# Central_Hub.net
KiCad netlist of a schematic drawn in EAGLE
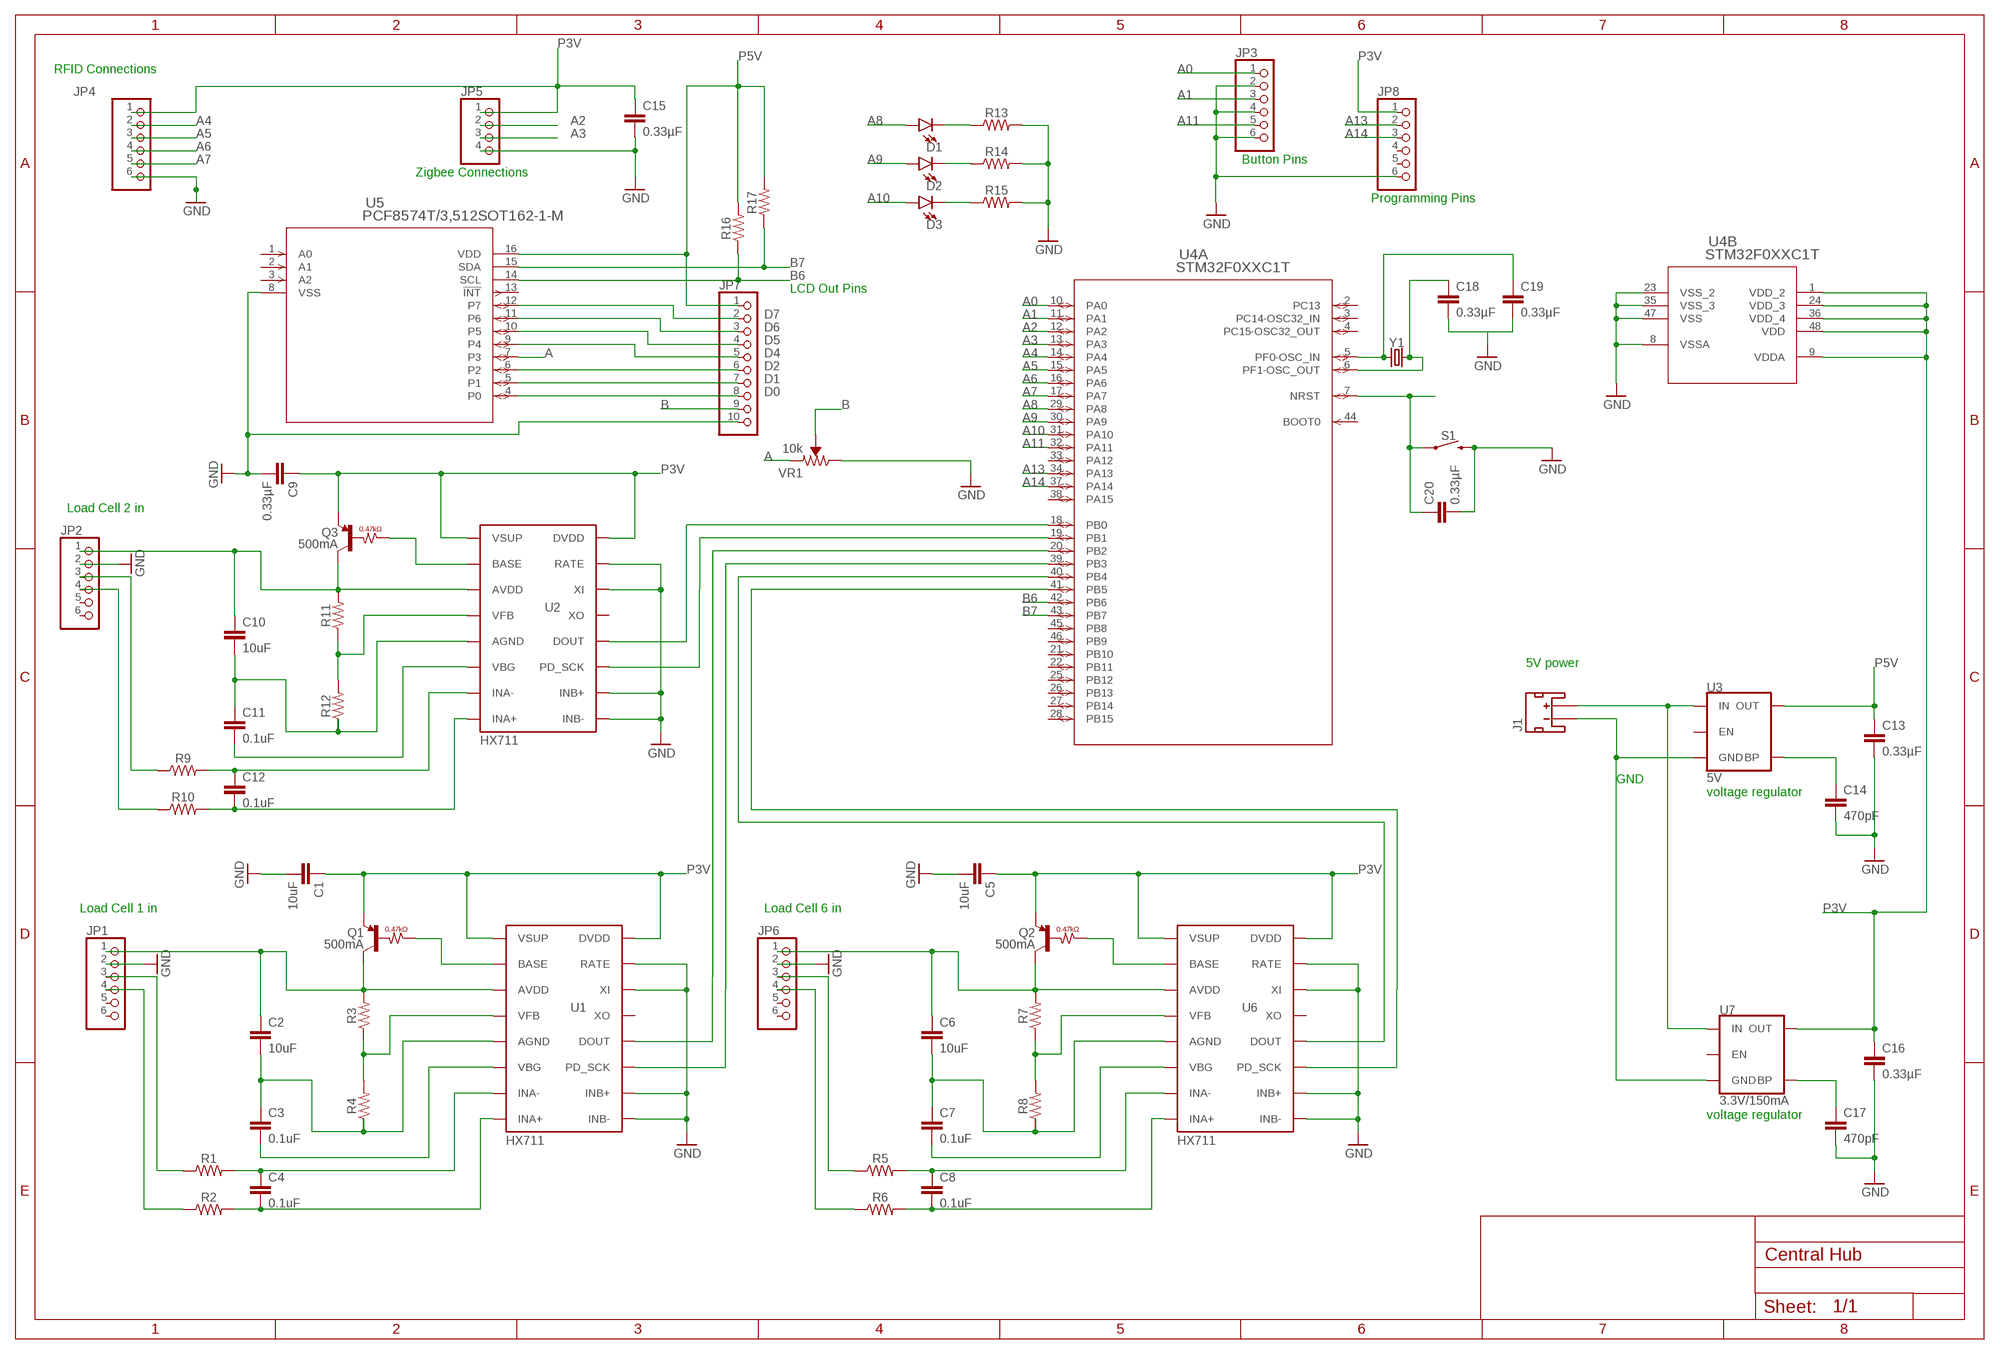
[diagram p0: schematic, sheet 1]

(export (version "E")
  (design (tool "Eeschema 10.0.6"))
  (components
    (comp (ref "C1")
      (value "10uF")
      (footprint "eagle-import:0603")
      (libsource (lib "eagle-import") (part "10UF-0603-6.3V-20%"))
    )
    (comp (ref "C2")
      (value "10uF")
      (footprint "eagle-import:0603")
      (libsource (lib "eagle-import") (part "10UF-0603-6.3V-20%"))
    )
    (comp (ref "C3")
      (value "0.1uF")
      (footprint "eagle-import:0603")
      (libsource (lib "eagle-import") (part "0.1UF-0603-25V-(+80/-20%)"))
    )
    (comp (ref "C4")
      (value "0.1uF")
      (footprint "eagle-import:0603")
      (libsource (lib "eagle-import") (part "0.1UF-0603-25V-(+80/-20%)"))
    )
    (comp (ref "C5")
      (value "10uF")
      (footprint "eagle-import:0603")
      (libsource (lib "eagle-import") (part "10UF-0603-6.3V-20%"))
    )
    (comp (ref "C6")
      (value "10uF")
      (footprint "eagle-import:0603")
      (libsource (lib "eagle-import") (part "10UF-0603-6.3V-20%"))
    )
    (comp (ref "C7")
      (value "0.1uF")
      (footprint "eagle-import:0603")
      (libsource (lib "eagle-import") (part "0.1UF-0603-25V-(+80/-20%)"))
    )
    (comp (ref "C8")
      (value "0.1uF")
      (footprint "eagle-import:0603")
      (libsource (lib "eagle-import") (part "0.1UF-0603-25V-(+80/-20%)"))
    )
    (comp (ref "C9")
      (value "0.33µF")
      (footprint "eagle-import:0805")
      (libsource (lib "eagle-import") (part "0.33UF/330NF-0805-50V-10%"))
    )
    (comp (ref "C10")
      (value "10uF")
      (footprint "eagle-import:0603")
      (libsource (lib "eagle-import") (part "10UF-0603-6.3V-20%"))
    )
    (comp (ref "C11")
      (value "0.1uF")
      (footprint "eagle-import:0603")
      (libsource (lib "eagle-import") (part "0.1UF-0603-25V-(+80/-20%)"))
    )
    (comp (ref "C12")
      (value "0.1uF")
      (footprint "eagle-import:0603")
      (libsource (lib "eagle-import") (part "0.1UF-0603-25V-(+80/-20%)"))
    )
    (comp (ref "C13")
      (value "0.33µF")
      (footprint "eagle-import:0805")
      (libsource (lib "eagle-import") (part "0.33UF/330NF-0805-50V-10%"))
    )
    (comp (ref "C14")
      (value "470pF")
      (footprint "eagle-import:0603")
      (libsource (lib "eagle-import") (part "470PF-0603-50V-5%"))
    )
    (comp (ref "C15")
      (value "0.33µF")
      (footprint "eagle-import:0805")
      (libsource (lib "eagle-import") (part "0.33UF/330NF-0805-50V-10%"))
    )
    (comp (ref "C16")
      (value "0.33µF")
      (footprint "eagle-import:0805")
      (libsource (lib "eagle-import") (part "0.33UF/330NF-0805-50V-10%"))
    )
    (comp (ref "C17")
      (value "470pF")
      (footprint "eagle-import:0603")
      (libsource (lib "eagle-import") (part "470PF-0603-50V-5%"))
    )
    (comp (ref "C18")
      (value "0.33µF")
      (footprint "eagle-import:0805")
      (libsource (lib "eagle-import") (part "0.33UF/330NF-0805-50V-10%"))
    )
    (comp (ref "C19")
      (value "0.33µF")
      (footprint "eagle-import:0805")
      (libsource (lib "eagle-import") (part "0.33UF/330NF-0805-50V-10%"))
    )
    (comp (ref "C20")
      (value "0.33µF")
      (footprint "eagle-import:0805")
      (libsource (lib "eagle-import") (part "0.33UF/330NF-0805-50V-10%"))
    )
    (comp (ref "D1")
      (value "LED5MM")
      (footprint "eagle-import:LED_5MM")
      (libsource (lib "eagle-import") (part "LED5MM"))
    )
    (comp (ref "D2")
      (value "LED5MM")
      (footprint "eagle-import:LED_5MM")
      (libsource (lib "eagle-import") (part "LED5MM"))
    )
    (comp (ref "D3")
      (value "LED5MM")
      (footprint "eagle-import:LED_5MM")
      (libsource (lib "eagle-import") (part "LED5MM"))
    )
    (comp (ref "J1")
      (value "JST_2MM_MALE")
      (footprint "eagle-import:JST-2-SMD")
      (libsource (lib "eagle-import") (part "JST_2MM_MALE"))
    )
    (comp (ref "JP1")
      (value "PINHD-1X6")
      (footprint "eagle-import:1X06")
      (libsource (lib "eagle-import") (part "PINHD-1X6"))
    )
    (comp (ref "JP2")
      (value "PINHD-1X6")
      (footprint "eagle-import:1X06")
      (libsource (lib "eagle-import") (part "PINHD-1X6"))
    )
    (comp (ref "JP3")
      (value "PINHD-1X6")
      (footprint "eagle-import:1X06")
      (libsource (lib "eagle-import") (part "PINHD-1X6"))
    )
    (comp (ref "JP4")
      (value "PINHD-1X6")
      (footprint "eagle-import:1X06")
      (libsource (lib "eagle-import") (part "PINHD-1X6"))
    )
    (comp (ref "JP5")
      (value "PINHD-1X4")
      (footprint "eagle-import:1X04")
      (libsource (lib "eagle-import") (part "PINHD-1X4"))
    )
    (comp (ref "JP6")
      (value "PINHD-1X6")
      (footprint "eagle-import:1X06")
      (libsource (lib "eagle-import") (part "PINHD-1X6"))
    )
    (comp (ref "JP7")
      (value "PINHD-1X10")
      (footprint "eagle-import:1X10")
      (libsource (lib "eagle-import") (part "PINHD-1X10"))
    )
    (comp (ref "JP8")
      (value "PINHD-1X6")
      (footprint "eagle-import:1X06")
      (libsource (lib "eagle-import") (part "PINHD-1X6"))
    )
    (comp (ref "Q1")
      (value "500mA")
      (footprint "eagle-import:SOT23-3")
      (libsource (lib "eagle-import") (part "TRANS_PNP_RES-DDTB142TC"))
    )
    (comp (ref "Q2")
      (value "500mA")
      (footprint "eagle-import:SOT23-3")
      (libsource (lib "eagle-import") (part "TRANS_PNP_RES-DDTB142TC"))
    )
    (comp (ref "Q3")
      (value "500mA")
      (footprint "eagle-import:SOT23-3")
      (libsource (lib "eagle-import") (part "TRANS_PNP_RES-DDTB142TC"))
    )
    (comp (ref "R1")
      (value "RESISTOR0603")
      (footprint "eagle-import:0603")
      (libsource (lib "eagle-import") (part "RESISTOR0603"))
    )
    (comp (ref "R2")
      (value "RESISTOR0603")
      (footprint "eagle-import:0603")
      (libsource (lib "eagle-import") (part "RESISTOR0603"))
    )
    (comp (ref "R3")
      (value "RESISTOR0603")
      (footprint "eagle-import:0603")
      (libsource (lib "eagle-import") (part "RESISTOR0603"))
    )
    (comp (ref "R4")
      (value "RESISTOR0603")
      (footprint "eagle-import:0603")
      (libsource (lib "eagle-import") (part "RESISTOR0603"))
    )
    (comp (ref "R5")
      (value "RESISTOR0603")
      (footprint "eagle-import:0603")
      (libsource (lib "eagle-import") (part "RESISTOR0603"))
    )
    (comp (ref "R6")
      (value "RESISTOR0603")
      (footprint "eagle-import:0603")
      (libsource (lib "eagle-import") (part "RESISTOR0603"))
    )
    (comp (ref "R7")
      (value "RESISTOR0603")
      (footprint "eagle-import:0603")
      (libsource (lib "eagle-import") (part "RESISTOR0603"))
    )
    (comp (ref "R8")
      (value "RESISTOR0603")
      (footprint "eagle-import:0603")
      (libsource (lib "eagle-import") (part "RESISTOR0603"))
    )
    (comp (ref "R9")
      (value "RESISTOR0603")
      (footprint "eagle-import:0603")
      (libsource (lib "eagle-import") (part "RESISTOR0603"))
    )
    (comp (ref "R10")
      (value "RESISTOR0603")
      (footprint "eagle-import:0603")
      (libsource (lib "eagle-import") (part "RESISTOR0603"))
    )
    (comp (ref "R11")
      (value "RESISTOR0603")
      (footprint "eagle-import:0603")
      (libsource (lib "eagle-import") (part "RESISTOR0603"))
    )
    (comp (ref "R12")
      (value "RESISTOR0603")
      (footprint "eagle-import:0603")
      (libsource (lib "eagle-import") (part "RESISTOR0603"))
    )
    (comp (ref "R13")
      (value "RESISTOR0603")
      (footprint "eagle-import:0603")
      (libsource (lib "eagle-import") (part "RESISTOR0603"))
    )
    (comp (ref "R14")
      (value "RESISTOR0603")
      (footprint "eagle-import:0603")
      (libsource (lib "eagle-import") (part "RESISTOR0603"))
    )
    (comp (ref "R15")
      (value "RESISTOR0603")
      (footprint "eagle-import:0603")
      (libsource (lib "eagle-import") (part "RESISTOR0603"))
    )
    (comp (ref "R16")
      (value "RESISTOR0603")
      (footprint "eagle-import:0603")
      (libsource (lib "eagle-import") (part "RESISTOR0603"))
    )
    (comp (ref "R17")
      (value "RESISTOR0603")
      (footprint "eagle-import:0603")
      (libsource (lib "eagle-import") (part "RESISTOR0603"))
    )
    (comp (ref "S1")
      (value "MOMENTARY-SWITCH-SPST-SMD-5.2MM")
      (footprint "eagle-import:TACTILE_SWITCH_SMD_5.2MM")
      (libsource (lib "eagle-import") (part "MOMENTARY-SWITCH-SPST-SMD-5.2MM"))
    )
    (comp (ref "U1")
      (value "HX711")
      (footprint "eagle-import:SO16")
      (libsource (lib "eagle-import") (part "HX711"))
    )
    (comp (ref "U2")
      (value "HX711")
      (footprint "eagle-import:SO16")
      (libsource (lib "eagle-import") (part "HX711"))
    )
    (comp (ref "U3")
      (value "5V")
      (footprint "eagle-import:SOT23-5")
      (libsource (lib "eagle-import") (part "V_REG_MIC52055V"))
    )
    (comp (ref "U4")
      (value "STM32F0XXC1T")
      (footprint "eagle-import:LQFP48-7X7MM")
      (fields (field (name "MANUFACTURER_PART_NUMBER") "stm32f0xxc1t"))
      (libsource (lib "eagle-import") (part "STM32F0XXC1T"))
    )
    (comp (ref "U5")
      (value "PCF8574T/3,512SOT162-1-M")
      (footprint "eagle-import:SOT162-1-M")
      (fields (field (name "MANUFACTURER_PART_NUMBER") "PCF8574T3512"))
      (libsource (lib "eagle-import") (part "PCF8574T/3,512SOT162-1-M"))
    )
    (comp (ref "U6")
      (value "HX711")
      (footprint "eagle-import:SO16")
      (libsource (lib "eagle-import") (part "HX711"))
    )
    (comp (ref "U7")
      (value "3.3V/150mA")
      (footprint "eagle-import:SOT23-5")
      (libsource (lib "eagle-import") (part "V_REG_MIC52053.3V"))
    )
    (comp (ref "VR1")
      (value "10k")
      (footprint "eagle-import:TRIMPOT-PTH-3386U")
      (libsource (lib "eagle-import") (part "TRIMPOT-PTH-10MM-KNOB-1/2W-10%"))
    )
    (comp (ref "Y1")
      (value "CRYSTALPTH-HC49US")
      (footprint "eagle-import:HC49US")
      (libsource (lib "eagle-import") (part "CRYSTALPTH-HC49US"))
    )
  )
  (nets
    (net (code "1") (name "/A") (class "Default")
      (node (ref "U5") (pin "7") (pinfunction "P3_7") (pintype "bidirectional"))
      (node (ref "VR1") (pin "1") (pinfunction "CCW_1") (pintype "passive"))
    )
    (net (code "2") (name "/A0") (class "Default")
      (node (ref "JP3") (pin "1") (pinfunction "1_1") (pintype "passive"))
      (node (ref "U4") (pin "10") (pinfunction "PA0_10") (pintype "bidirectional"))
    )
    (net (code "3") (name "/A1") (class "Default")
      (node (ref "JP3") (pin "3") (pinfunction "3_3") (pintype "passive"))
      (node (ref "U4") (pin "11") (pinfunction "PA1_11") (pintype "bidirectional"))
    )
    (net (code "4") (name "/A2") (class "Default")
      (node (ref "JP5") (pin "2") (pinfunction "2_2") (pintype "passive"))
      (node (ref "U4") (pin "12") (pinfunction "PA2_12") (pintype "bidirectional"))
    )
    (net (code "5") (name "/A3") (class "Default")
      (node (ref "JP5") (pin "3") (pinfunction "3_3") (pintype "passive"))
      (node (ref "U4") (pin "13") (pinfunction "PA3_13") (pintype "bidirectional"))
    )
    (net (code "6") (name "/A4") (class "Default")
      (node (ref "JP4") (pin "2") (pinfunction "2_2") (pintype "passive"))
      (node (ref "U4") (pin "14") (pinfunction "PA4_14") (pintype "bidirectional"))
    )
    (net (code "7") (name "/A5") (class "Default")
      (node (ref "JP4") (pin "3") (pinfunction "3_3") (pintype "passive"))
      (node (ref "U4") (pin "15") (pinfunction "PA5_15") (pintype "bidirectional"))
    )
    (net (code "8") (name "/A6") (class "Default")
      (node (ref "JP4") (pin "4") (pinfunction "4_4") (pintype "passive"))
      (node (ref "U4") (pin "16") (pinfunction "PA6_16") (pintype "bidirectional"))
    )
    (net (code "9") (name "/A7") (class "Default")
      (node (ref "JP4") (pin "5") (pinfunction "5_5") (pintype "passive"))
      (node (ref "U4") (pin "17") (pinfunction "PA7_17") (pintype "bidirectional"))
    )
    (net (code "10") (name "/A8") (class "Default")
      (node (ref "D1") (pin "A") (pinfunction "A_A") (pintype "passive"))
      (node (ref "U4") (pin "29") (pinfunction "PA8_29") (pintype "bidirectional"))
    )
    (net (code "11") (name "/A9") (class "Default")
      (node (ref "D2") (pin "A") (pinfunction "A_A") (pintype "passive"))
      (node (ref "U4") (pin "30") (pinfunction "PA9_30") (pintype "bidirectional"))
    )
    (net (code "12") (name "/A10") (class "Default")
      (node (ref "D3") (pin "A") (pinfunction "A_A") (pintype "passive"))
      (node (ref "U4") (pin "31") (pinfunction "PA10_31") (pintype "bidirectional"))
    )
    (net (code "13") (name "/A11") (class "Default")
      (node (ref "JP3") (pin "5") (pinfunction "5_5") (pintype "passive"))
      (node (ref "U4") (pin "32") (pinfunction "PA11_32") (pintype "bidirectional"))
    )
    (net (code "14") (name "/A13") (class "Default")
      (node (ref "JP8") (pin "2") (pinfunction "2_2") (pintype "passive"))
      (node (ref "U4") (pin "34") (pinfunction "PA13_34") (pintype "bidirectional"))
    )
    (net (code "15") (name "/A14") (class "Default")
      (node (ref "JP8") (pin "3") (pinfunction "3_3") (pintype "passive"))
      (node (ref "U4") (pin "37") (pinfunction "PA14_37") (pintype "bidirectional"))
    )
    (net (code "16") (name "/B") (class "Default")
      (node (ref "JP7") (pin "9") (pinfunction "9_9") (pintype "passive"))
      (node (ref "VR1") (pin "2") (pinfunction "WIPER_2") (pintype "passive"))
    )
    (net (code "17") (name "/B6") (class "Default")
      (node (ref "R16") (pin "1") (pinfunction "1_1") (pintype "passive"))
      (node (ref "U4") (pin "42") (pinfunction "PB6_42") (pintype "bidirectional"))
      (node (ref "U5") (pin "14") (pinfunction "SCL_14") (pintype "passive"))
    )
    (net (code "18") (name "/B7") (class "Default")
      (node (ref "R17") (pin "1") (pinfunction "1_1") (pintype "passive"))
      (node (ref "U4") (pin "43") (pinfunction "PB7_43") (pintype "bidirectional"))
      (node (ref "U5") (pin "15") (pinfunction "SDA_15") (pintype "passive"))
    )
    (net (code "19") (name "/D0") (class "Default")
      (node (ref "JP7") (pin "8") (pinfunction "8_8") (pintype "passive"))
      (node (ref "U5") (pin "4") (pinfunction "P0_4") (pintype "bidirectional"))
    )
    (net (code "20") (name "/D1") (class "Default")
      (node (ref "JP7") (pin "7") (pinfunction "7_7") (pintype "passive"))
      (node (ref "U5") (pin "5") (pinfunction "P1_5") (pintype "bidirectional"))
    )
    (net (code "21") (name "/D2") (class "Default")
      (node (ref "JP7") (pin "6") (pinfunction "6_6") (pintype "passive"))
      (node (ref "U5") (pin "6") (pinfunction "P2_6") (pintype "bidirectional"))
    )
    (net (code "22") (name "/D4") (class "Default")
      (node (ref "JP7") (pin "5") (pinfunction "5_5") (pintype "passive"))
      (node (ref "U5") (pin "9") (pinfunction "P4_9") (pintype "bidirectional"))
    )
    (net (code "23") (name "/D5") (class "Default")
      (node (ref "JP7") (pin "4") (pinfunction "4_4") (pintype "passive"))
      (node (ref "U5") (pin "10") (pinfunction "P5_10") (pintype "bidirectional"))
    )
    (net (code "24") (name "/D6") (class "Default")
      (node (ref "JP7") (pin "3") (pinfunction "3_3") (pintype "passive"))
      (node (ref "U5") (pin "11") (pinfunction "P6_11") (pintype "bidirectional"))
    )
    (net (code "25") (name "/D7") (class "Default")
      (node (ref "JP7") (pin "2") (pinfunction "2_2") (pintype "passive"))
      (node (ref "U5") (pin "12") (pinfunction "P7_12") (pintype "bidirectional"))
    )
    (net (code "26") (name "/P3V") (class "Default")
      (node (ref "C1") (pin "1") (pinfunction "1_1") (pintype "passive"))
      (node (ref "C15") (pin "1") (pinfunction "1_1") (pintype "passive"))
      (node (ref "C16") (pin "1") (pinfunction "1_1") (pintype "passive"))
      (node (ref "C5") (pin "1") (pinfunction "1_1") (pintype "passive"))
      (node (ref "C9") (pin "1") (pinfunction "1_1") (pintype "passive"))
      (node (ref "JP4") (pin "1") (pinfunction "1_1") (pintype "passive"))
      (node (ref "JP5") (pin "1") (pinfunction "1_1") (pintype "passive"))
      (node (ref "JP8") (pin "1") (pinfunction "1_1") (pintype "passive"))
      (node (ref "Q1") (pin "2") (pinfunction "E_2") (pintype "passive"))
      (node (ref "Q2") (pin "2") (pinfunction "E_2") (pintype "passive"))
      (node (ref "Q3") (pin "2") (pinfunction "E_2") (pintype "passive"))
      (node (ref "U1") (pin "1") (pinfunction "VSUP_1") (pintype "bidirectional"))
      (node (ref "U1") (pin "16") (pinfunction "DVDD_16") (pintype "bidirectional"))
      (node (ref "U2") (pin "1") (pinfunction "VSUP_1") (pintype "bidirectional"))
      (node (ref "U2") (pin "16") (pinfunction "DVDD_16") (pintype "bidirectional"))
      (node (ref "U4") (pin "1") (pinfunction "VDD_2_1") (pintype "power_in"))
      (node (ref "U4") (pin "24") (pinfunction "VDD_3_24") (pintype "power_in"))
      (node (ref "U4") (pin "36") (pinfunction "VDD_4_36") (pintype "power_in"))
      (node (ref "U4") (pin "48") (pinfunction "VDD_48") (pintype "power_in"))
      (node (ref "U4") (pin "9") (pinfunction "VDDA_9") (pintype "power_in"))
      (node (ref "U6") (pin "1") (pinfunction "VSUP_1") (pintype "bidirectional"))
      (node (ref "U6") (pin "16") (pinfunction "DVDD_16") (pintype "bidirectional"))
      (node (ref "U7") (pin "5") (pinfunction "OUT_5") (pintype "passive"))
    )
    (net (code "27") (name "/P5V") (class "Default")
      (node (ref "C13") (pin "1") (pinfunction "1_1") (pintype "passive"))
      (node (ref "JP7") (pin "1") (pinfunction "1_1") (pintype "passive"))
      (node (ref "R16") (pin "2") (pinfunction "2_2") (pintype "passive"))
      (node (ref "R17") (pin "2") (pinfunction "2_2") (pintype "passive"))
      (node (ref "U3") (pin "5") (pinfunction "OUT_5") (pintype "passive"))
      (node (ref "U5") (pin "16") (pinfunction "VDD_16") (pintype "power_in"))
    )
    (net (code "28") (name "GND") (class "Default")
      (node (ref "C1") (pin "2") (pinfunction "2_2") (pintype "passive"))
      (node (ref "C13") (pin "2") (pinfunction "2_2") (pintype "passive"))
      (node (ref "C14") (pin "2") (pinfunction "2_2") (pintype "passive"))
      (node (ref "C15") (pin "2") (pinfunction "2_2") (pintype "passive"))
      (node (ref "C16") (pin "2") (pinfunction "2_2") (pintype "passive"))
      (node (ref "C17") (pin "2") (pinfunction "2_2") (pintype "passive"))
      (node (ref "C18") (pin "2") (pinfunction "2_2") (pintype "passive"))
      (node (ref "C19") (pin "2") (pinfunction "2_2") (pintype "passive"))
      (node (ref "C20") (pin "2") (pinfunction "2_2") (pintype "passive"))
      (node (ref "C5") (pin "2") (pinfunction "2_2") (pintype "passive"))
      (node (ref "C9") (pin "2") (pinfunction "2_2") (pintype "passive"))
      (node (ref "JP1") (pin "2") (pinfunction "2_2") (pintype "passive"))
      (node (ref "JP2") (pin "2") (pinfunction "2_2") (pintype "passive"))
      (node (ref "JP3") (pin "2") (pinfunction "2_2") (pintype "passive"))
      (node (ref "JP3") (pin "4") (pinfunction "4_4") (pintype "passive"))
      (node (ref "JP3") (pin "6") (pinfunction "6_6") (pintype "passive"))
      (node (ref "JP4") (pin "6") (pinfunction "6_6") (pintype "passive"))
      (node (ref "JP5") (pin "4") (pinfunction "4_4") (pintype "passive"))
      (node (ref "JP6") (pin "2") (pinfunction "2_2") (pintype "passive"))
      (node (ref "JP7") (pin "10") (pinfunction "10_10") (pintype "passive"))
      (node (ref "JP8") (pin "6") (pinfunction "6_6") (pintype "passive"))
      (node (ref "R13") (pin "2") (pinfunction "2_2") (pintype "passive"))
      (node (ref "R14") (pin "2") (pinfunction "2_2") (pintype "passive"))
      (node (ref "R15") (pin "2") (pinfunction "2_2") (pintype "passive"))
      (node (ref "S1") (pin "3") (pinfunction "2_3") (pintype "passive"))
      (node (ref "U1") (pin "10") (pinfunction "INB+_10") (pintype "bidirectional"))
      (node (ref "U1") (pin "14") (pinfunction "XI_14") (pintype "bidirectional"))
      (node (ref "U1") (pin "15") (pinfunction "RATE_15") (pintype "bidirectional"))
      (node (ref "U1") (pin "9") (pinfunction "INB-_9") (pintype "bidirectional"))
      (node (ref "U2") (pin "10") (pinfunction "INB+_10") (pintype "bidirectional"))
      (node (ref "U2") (pin "14") (pinfunction "XI_14") (pintype "bidirectional"))
      (node (ref "U2") (pin "15") (pinfunction "RATE_15") (pintype "bidirectional"))
      (node (ref "U2") (pin "9") (pinfunction "INB-_9") (pintype "bidirectional"))
      (node (ref "U4") (pin "23") (pinfunction "VSS_2_23") (pintype "power_in"))
      (node (ref "U4") (pin "35") (pinfunction "VSS_3_35") (pintype "power_in"))
      (node (ref "U4") (pin "47") (pinfunction "VSS_47") (pintype "power_in"))
      (node (ref "U4") (pin "8") (pinfunction "VSSA_8") (pintype "power_in"))
      (node (ref "U5") (pin "8") (pinfunction "VSS_8") (pintype "power_in"))
      (node (ref "U6") (pin "10") (pinfunction "INB+_10") (pintype "bidirectional"))
      (node (ref "U6") (pin "14") (pinfunction "XI_14") (pintype "bidirectional"))
      (node (ref "U6") (pin "15") (pinfunction "RATE_15") (pintype "bidirectional"))
      (node (ref "U6") (pin "9") (pinfunction "INB-_9") (pintype "bidirectional"))
      (node (ref "VR1") (pin "3") (pinfunction "CW_3") (pintype "passive"))
    )
    (net (code "29") (name "Net-(D1-C)") (class "Default")
      (node (ref "D1") (pin "K") (pinfunction "C_K") (pintype "passive"))
      (node (ref "R13") (pin "1") (pinfunction "1_1") (pintype "passive"))
    )
    (net (code "30") (name "Net-(D2-C)") (class "Default")
      (node (ref "D2") (pin "K") (pinfunction "C_K") (pintype "passive"))
      (node (ref "R14") (pin "1") (pinfunction "1_1") (pintype "passive"))
    )
    (net (code "31") (name "Net-(D3-C)") (class "Default")
      (node (ref "D3") (pin "K") (pinfunction "C_K") (pintype "passive"))
      (node (ref "R15") (pin "1") (pinfunction "1_1") (pintype "passive"))
    )
    (net (code "32") (name "Net-(J1-+)") (class "Default")
      (node (ref "J1") (pin "2") (pinfunction "+_2") (pintype "bidirectional"))
      (node (ref "U3") (pin "1") (pinfunction "IN_1") (pintype "input"))
      (node (ref "U7") (pin "1") (pinfunction "IN_1") (pintype "input"))
    )
    (net (code "33") (name "Net-(J1--)") (class "Default")
      (node (ref "J1") (pin "1") (pinfunction "-_1") (pintype "bidirectional"))
      (node (ref "U3") (pin "2") (pinfunction "GND_2") (pintype "input"))
      (node (ref "U7") (pin "2") (pinfunction "GND_2") (pintype "input"))
    )
    (net (code "34") (name "Net-(JP1-Pad3)") (class "Default")
      (node (ref "JP1") (pin "3") (pinfunction "3_3") (pintype "passive"))
      (node (ref "R1") (pin "1") (pinfunction "1_1") (pintype "passive"))
    )
    (net (code "35") (name "Net-(JP1-Pad4)") (class "Default")
      (node (ref "JP1") (pin "4") (pinfunction "4_4") (pintype "passive"))
      (node (ref "R2") (pin "1") (pinfunction "1_1") (pintype "passive"))
    )
    (net (code "36") (name "Net-(JP2-Pad3)") (class "Default")
      (node (ref "JP2") (pin "3") (pinfunction "3_3") (pintype "passive"))
      (node (ref "R9") (pin "1") (pinfunction "1_1") (pintype "passive"))
    )
    (net (code "37") (name "Net-(JP2-Pad4)") (class "Default")
      (node (ref "JP2") (pin "4") (pinfunction "4_4") (pintype "passive"))
      (node (ref "R10") (pin "1") (pinfunction "1_1") (pintype "passive"))
    )
    (net (code "38") (name "Net-(JP6-Pad3)") (class "Default")
      (node (ref "JP6") (pin "3") (pinfunction "3_3") (pintype "passive"))
      (node (ref "R5") (pin "1") (pinfunction "1_1") (pintype "passive"))
    )
    (net (code "39") (name "Net-(JP6-Pad4)") (class "Default")
      (node (ref "JP6") (pin "4") (pinfunction "4_4") (pintype "passive"))
      (node (ref "R6") (pin "1") (pinfunction "1_1") (pintype "passive"))
    )
    (net (code "40") (name "Net-(Q1-B)") (class "Default")
      (node (ref "Q1") (pin "1") (pinfunction "B_1") (pintype "passive"))
      (node (ref "U1") (pin "2") (pinfunction "BASE_2") (pintype "bidirectional"))
    )
    (net (code "41") (name "Net-(Q1-C)") (class "Default")
      (node (ref "C2") (pin "1") (pinfunction "1_1") (pintype "passive"))
      (node (ref "JP1") (pin "1") (pinfunction "1_1") (pintype "passive"))
      (node (ref "Q1") (pin "3") (pinfunction "C_3") (pintype "passive"))
      (node (ref "R3") (pin "2") (pinfunction "2_2") (pintype "passive"))
      (node (ref "U1") (pin "3") (pinfunction "AVDD_3") (pintype "bidirectional"))
    )
    (net (code "42") (name "Net-(Q2-B)") (class "Default")
      (node (ref "Q2") (pin "1") (pinfunction "B_1") (pintype "passive"))
      (node (ref "U6") (pin "2") (pinfunction "BASE_2") (pintype "bidirectional"))
    )
    (net (code "43") (name "Net-(Q2-C)") (class "Default")
      (node (ref "C6") (pin "1") (pinfunction "1_1") (pintype "passive"))
      (node (ref "JP6") (pin "1") (pinfunction "1_1") (pintype "passive"))
      (node (ref "Q2") (pin "3") (pinfunction "C_3") (pintype "passive"))
      (node (ref "R7") (pin "2") (pinfunction "2_2") (pintype "passive"))
      (node (ref "U6") (pin "3") (pinfunction "AVDD_3") (pintype "bidirectional"))
    )
    (net (code "44") (name "Net-(Q3-B)") (class "Default")
      (node (ref "Q3") (pin "1") (pinfunction "B_1") (pintype "passive"))
      (node (ref "U2") (pin "2") (pinfunction "BASE_2") (pintype "bidirectional"))
    )
    (net (code "45") (name "Net-(Q3-C)") (class "Default")
      (node (ref "C10") (pin "1") (pinfunction "1_1") (pintype "passive"))
      (node (ref "JP2") (pin "1") (pinfunction "1_1") (pintype "passive"))
      (node (ref "Q3") (pin "3") (pinfunction "C_3") (pintype "passive"))
      (node (ref "R11") (pin "2") (pinfunction "2_2") (pintype "passive"))
      (node (ref "U2") (pin "3") (pinfunction "AVDD_3") (pintype "bidirectional"))
    )
    (net (code "46") (name "Net-(U1-AGND)") (class "Default")
      (node (ref "C2") (pin "2") (pinfunction "2_2") (pintype "passive"))
      (node (ref "C3") (pin "1") (pinfunction "1_1") (pintype "passive"))
      (node (ref "R4") (pin "1") (pinfunction "1_1") (pintype "passive"))
      (node (ref "U1") (pin "5") (pinfunction "AGND_5") (pintype "bidirectional"))
    )
    (net (code "47") (name "Net-(U1-DOUT)") (class "Default")
      (node (ref "U1") (pin "12") (pinfunction "DOUT_12") (pintype "bidirectional"))
      (node (ref "U4") (pin "20") (pinfunction "PB2_20") (pintype "bidirectional"))
    )
    (net (code "48") (name "Net-(U1-INA+)") (class "Default")
      (node (ref "C4") (pin "2") (pinfunction "2_2") (pintype "passive"))
      (node (ref "R2") (pin "2") (pinfunction "2_2") (pintype "passive"))
      (node (ref "U1") (pin "8") (pinfunction "INA+_8") (pintype "bidirectional"))
    )
    (net (code "49") (name "Net-(U1-INA-)") (class "Default")
      (node (ref "C4") (pin "1") (pinfunction "1_1") (pintype "passive"))
      (node (ref "R1") (pin "2") (pinfunction "2_2") (pintype "passive"))
      (node (ref "U1") (pin "7") (pinfunction "INA-_7") (pintype "bidirectional"))
    )
    (net (code "50") (name "Net-(U1-PD_SCK)") (class "Default")
      (node (ref "U1") (pin "11") (pinfunction "PD_SCK_11") (pintype "bidirectional"))
      (node (ref "U4") (pin "39") (pinfunction "PB3_39") (pintype "bidirectional"))
    )
    (net (code "51") (name "Net-(U1-VBG)") (class "Default")
      (node (ref "C3") (pin "2") (pinfunction "2_2") (pintype "passive"))
      (node (ref "U1") (pin "6") (pinfunction "VBG_6") (pintype "bidirectional"))
    )
    (net (code "52") (name "Net-(U1-VFB)") (class "Default")
      (node (ref "R3") (pin "1") (pinfunction "1_1") (pintype "passive"))
      (node (ref "R4") (pin "2") (pinfunction "2_2") (pintype "passive"))
      (node (ref "U1") (pin "4") (pinfunction "VFB_4") (pintype "bidirectional"))
    )
    (net (code "53") (name "Net-(U2-AGND)") (class "Default")
      (node (ref "C10") (pin "2") (pinfunction "2_2") (pintype "passive"))
      (node (ref "C11") (pin "1") (pinfunction "1_1") (pintype "passive"))
      (node (ref "R12") (pin "1") (pinfunction "1_1") (pintype "passive"))
      (node (ref "U2") (pin "5") (pinfunction "AGND_5") (pintype "bidirectional"))
    )
    (net (code "54") (name "Net-(U2-DOUT)") (class "Default")
      (node (ref "U2") (pin "12") (pinfunction "DOUT_12") (pintype "bidirectional"))
      (node (ref "U4") (pin "18") (pinfunction "PB0_18") (pintype "bidirectional"))
    )
    (net (code "55") (name "Net-(U2-INA+)") (class "Default")
      (node (ref "C12") (pin "2") (pinfunction "2_2") (pintype "passive"))
      (node (ref "R10") (pin "2") (pinfunction "2_2") (pintype "passive"))
      (node (ref "U2") (pin "8") (pinfunction "INA+_8") (pintype "bidirectional"))
    )
    (net (code "56") (name "Net-(U2-INA-)") (class "Default")
      (node (ref "C12") (pin "1") (pinfunction "1_1") (pintype "passive"))
      (node (ref "R9") (pin "2") (pinfunction "2_2") (pintype "passive"))
      (node (ref "U2") (pin "7") (pinfunction "INA-_7") (pintype "bidirectional"))
    )
    (net (code "57") (name "Net-(U2-PD_SCK)") (class "Default")
      (node (ref "U2") (pin "11") (pinfunction "PD_SCK_11") (pintype "bidirectional"))
      (node (ref "U4") (pin "19") (pinfunction "PB1_19") (pintype "bidirectional"))
    )
    (net (code "58") (name "Net-(U2-VBG)") (class "Default")
      (node (ref "C11") (pin "2") (pinfunction "2_2") (pintype "passive"))
      (node (ref "U2") (pin "6") (pinfunction "VBG_6") (pintype "bidirectional"))
    )
    (net (code "59") (name "Net-(U2-VFB)") (class "Default")
      (node (ref "R11") (pin "1") (pinfunction "1_1") (pintype "passive"))
      (node (ref "R12") (pin "2") (pinfunction "2_2") (pintype "passive"))
      (node (ref "U2") (pin "4") (pinfunction "VFB_4") (pintype "bidirectional"))
    )
    (net (code "60") (name "Net-(U3-BP)") (class "Default")
      (node (ref "C14") (pin "1") (pinfunction "1_1") (pintype "passive"))
      (node (ref "U3") (pin "4") (pinfunction "BP_4") (pintype "input"))
    )
    (net (code "61") (name "Net-(U4A-NRST)") (class "Default")
      (node (ref "C20") (pin "1") (pinfunction "1_1") (pintype "passive"))
      (node (ref "S1") (pin "1") (pinfunction "1_1") (pintype "passive"))
      (node (ref "U4") (pin "7") (pinfunction "NRST_7") (pintype "bidirectional"))
    )
    (net (code "62") (name "Net-(U4A-PB4)") (class "Default")
      (node (ref "U4") (pin "40") (pinfunction "PB4_40") (pintype "bidirectional"))
      (node (ref "U6") (pin "12") (pinfunction "DOUT_12") (pintype "bidirectional"))
    )
    (net (code "63") (name "Net-(U4A-PB5)") (class "Default")
      (node (ref "U4") (pin "41") (pinfunction "PB5_41") (pintype "bidirectional"))
      (node (ref "U6") (pin "11") (pinfunction "PD_SCK_11") (pintype "bidirectional"))
    )
    (net (code "64") (name "Net-(U4A-PF0-OSC_IN)") (class "Default")
      (node (ref "C19") (pin "1") (pinfunction "1_1") (pintype "passive"))
      (node (ref "U4") (pin "5") (pinfunction "PF0-OSC_IN_5") (pintype "bidirectional"))
      (node (ref "Y1") (pin "1") (pinfunction "1_1") (pintype "passive"))
    )
    (net (code "65") (name "Net-(U4A-PF1-OSC_OUT)") (class "Default")
      (node (ref "C18") (pin "1") (pinfunction "1_1") (pintype "passive"))
      (node (ref "U4") (pin "6") (pinfunction "PF1-OSC_OUT_6") (pintype "bidirectional"))
      (node (ref "Y1") (pin "2") (pinfunction "2_2") (pintype "passive"))
    )
    (net (code "66") (name "Net-(U6-AGND)") (class "Default")
      (node (ref "C6") (pin "2") (pinfunction "2_2") (pintype "passive"))
      (node (ref "C7") (pin "1") (pinfunction "1_1") (pintype "passive"))
      (node (ref "R8") (pin "1") (pinfunction "1_1") (pintype "passive"))
      (node (ref "U6") (pin "5") (pinfunction "AGND_5") (pintype "bidirectional"))
    )
    (net (code "67") (name "Net-(U6-INA+)") (class "Default")
      (node (ref "C8") (pin "2") (pinfunction "2_2") (pintype "passive"))
      (node (ref "R6") (pin "2") (pinfunction "2_2") (pintype "passive"))
      (node (ref "U6") (pin "8") (pinfunction "INA+_8") (pintype "bidirectional"))
    )
    (net (code "68") (name "Net-(U6-INA-)") (class "Default")
      (node (ref "C8") (pin "1") (pinfunction "1_1") (pintype "passive"))
      (node (ref "R5") (pin "2") (pinfunction "2_2") (pintype "passive"))
      (node (ref "U6") (pin "7") (pinfunction "INA-_7") (pintype "bidirectional"))
    )
    (net (code "69") (name "Net-(U6-VBG)") (class "Default")
      (node (ref "C7") (pin "2") (pinfunction "2_2") (pintype "passive"))
      (node (ref "U6") (pin "6") (pinfunction "VBG_6") (pintype "bidirectional"))
    )
    (net (code "70") (name "Net-(U6-VFB)") (class "Default")
      (node (ref "R7") (pin "1") (pinfunction "1_1") (pintype "passive"))
      (node (ref "R8") (pin "2") (pinfunction "2_2") (pintype "passive"))
      (node (ref "U6") (pin "4") (pinfunction "VFB_4") (pintype "bidirectional"))
    )
    (net (code "71") (name "Net-(U7-BP)") (class "Default")
      (node (ref "C17") (pin "1") (pinfunction "1_1") (pintype "passive"))
      (node (ref "U7") (pin "4") (pinfunction "BP_4") (pintype "input"))
    )
    (net (code "72") (name "unconnected-(J1-PAD1-PadNC1)") (class "Default")
      (node (ref "J1") (pin "NC1") (pinfunction "PAD1_NC1") (pintype "bidirectional"))
    )
    (net (code "73") (name "unconnected-(J1-PAD2-PadNC2)") (class "Default")
      (node (ref "J1") (pin "NC2") (pinfunction "PAD2_NC2") (pintype "bidirectional"))
    )
    (net (code "74") (name "unconnected-(JP1-Pad5)") (class "Default")
      (node (ref "JP1") (pin "5") (pinfunction "5_5") (pintype "passive"))
    )
    (net (code "75") (name "unconnected-(JP1-Pad6)") (class "Default")
      (node (ref "JP1") (pin "6") (pinfunction "6_6") (pintype "passive"))
    )
    (net (code "76") (name "unconnected-(JP2-Pad5)") (class "Default")
      (node (ref "JP2") (pin "5") (pinfunction "5_5") (pintype "passive"))
    )
    (net (code "77") (name "unconnected-(JP2-Pad6)") (class "Default")
      (node (ref "JP2") (pin "6") (pinfunction "6_6") (pintype "passive"))
    )
    (net (code "78") (name "unconnected-(JP6-Pad5)") (class "Default")
      (node (ref "JP6") (pin "5") (pinfunction "5_5") (pintype "passive"))
    )
    (net (code "79") (name "unconnected-(JP6-Pad6)") (class "Default")
      (node (ref "JP6") (pin "6") (pinfunction "6_6") (pintype "passive"))
    )
    (net (code "80") (name "unconnected-(JP8-Pad4)") (class "Default")
      (node (ref "JP8") (pin "4") (pinfunction "4_4") (pintype "passive"))
    )
    (net (code "81") (name "unconnected-(JP8-Pad5)") (class "Default")
      (node (ref "JP8") (pin "5") (pinfunction "5_5") (pintype "passive"))
    )
    (net (code "82") (name "unconnected-(U1-XO-Pad13)") (class "Default")
      (node (ref "U1") (pin "13") (pinfunction "XO_13") (pintype "bidirectional"))
    )
    (net (code "83") (name "unconnected-(U2-XO-Pad13)") (class "Default")
      (node (ref "U2") (pin "13") (pinfunction "XO_13") (pintype "bidirectional"))
    )
    (net (code "84") (name "unconnected-(U3-EN-Pad3)") (class "Default")
      (node (ref "U3") (pin "3") (pinfunction "EN_3") (pintype "input"))
    )
    (net (code "85") (name "unconnected-(U4A-BOOT0-Pad44)") (class "Default")
      (node (ref "U4") (pin "44") (pinfunction "BOOT0_44") (pintype "input"))
    )
    (net (code "86") (name "unconnected-(U4A-PA12-Pad33)") (class "Default")
      (node (ref "U4") (pin "33") (pinfunction "PA12_33") (pintype "bidirectional"))
    )
    (net (code "87") (name "unconnected-(U4A-PA15-Pad38)") (class "Default")
      (node (ref "U4") (pin "38") (pinfunction "PA15_38") (pintype "bidirectional"))
    )
    (net (code "88") (name "unconnected-(U4A-PB8-Pad45)") (class "Default")
      (node (ref "U4") (pin "45") (pinfunction "PB8_45") (pintype "bidirectional"))
    )
    (net (code "89") (name "unconnected-(U4A-PB9-Pad46)") (class "Default")
      (node (ref "U4") (pin "46") (pinfunction "PB9_46") (pintype "bidirectional"))
    )
    (net (code "90") (name "unconnected-(U4A-PB10-Pad21)") (class "Default")
      (node (ref "U4") (pin "21") (pinfunction "PB10_21") (pintype "bidirectional"))
    )
    (net (code "91") (name "unconnected-(U4A-PB11-Pad22)") (class "Default")
      (node (ref "U4") (pin "22") (pinfunction "PB11_22") (pintype "bidirectional"))
    )
    (net (code "92") (name "unconnected-(U4A-PB12-Pad25)") (class "Default")
      (node (ref "U4") (pin "25") (pinfunction "PB12_25") (pintype "bidirectional"))
    )
    (net (code "93") (name "unconnected-(U4A-PB13-Pad26)") (class "Default")
      (node (ref "U4") (pin "26") (pinfunction "PB13_26") (pintype "bidirectional"))
    )
    (net (code "94") (name "unconnected-(U4A-PB14-Pad27)") (class "Default")
      (node (ref "U4") (pin "27") (pinfunction "PB14_27") (pintype "bidirectional"))
    )
    (net (code "95") (name "unconnected-(U4A-PB15-Pad28)") (class "Default")
      (node (ref "U4") (pin "28") (pinfunction "PB15_28") (pintype "bidirectional"))
    )
    (net (code "96") (name "unconnected-(U4A-PC13-Pad2)") (class "Default")
      (node (ref "U4") (pin "2") (pinfunction "PC13_2") (pintype "bidirectional"))
    )
    (net (code "97") (name "unconnected-(U4A-PC14-OSC32_IN-Pad3)") (class "Default")
      (node (ref "U4") (pin "3") (pinfunction "PC14-OSC32_IN_3") (pintype "bidirectional"))
    )
    (net (code "98") (name "unconnected-(U4A-PC15-OSC32_OUT-Pad4)") (class "Default")
      (node (ref "U4") (pin "4") (pinfunction "PC15-OSC32_OUT_4") (pintype "bidirectional"))
    )
    (net (code "99") (name "unconnected-(U5-A0-Pad1)") (class "Default")
      (node (ref "U5") (pin "1") (pinfunction "A0_1") (pintype "input"))
    )
    (net (code "100") (name "unconnected-(U5-A1-Pad2)") (class "Default")
      (node (ref "U5") (pin "2") (pinfunction "A1_2") (pintype "input"))
    )
    (net (code "101") (name "unconnected-(U5-A2-Pad3)") (class "Default")
      (node (ref "U5") (pin "3") (pinfunction "A2_3") (pintype "input"))
    )
    (net (code "102") (name "unconnected-(U5-~{INT}-Pad13)") (class "Default")
      (node (ref "U5") (pin "13") (pinfunction "~{INT}_13") (pintype "output"))
    )
    (net (code "103") (name "unconnected-(U6-XO-Pad13)") (class "Default")
      (node (ref "U6") (pin "13") (pinfunction "XO_13") (pintype "bidirectional"))
    )
    (net (code "104") (name "unconnected-(U7-EN-Pad3)") (class "Default")
      (node (ref "U7") (pin "3") (pinfunction "EN_3") (pintype "input"))
    )
  )
)
